# motorDriverv2.net
KiCad netlist of a schematic drawn in Altium Designer
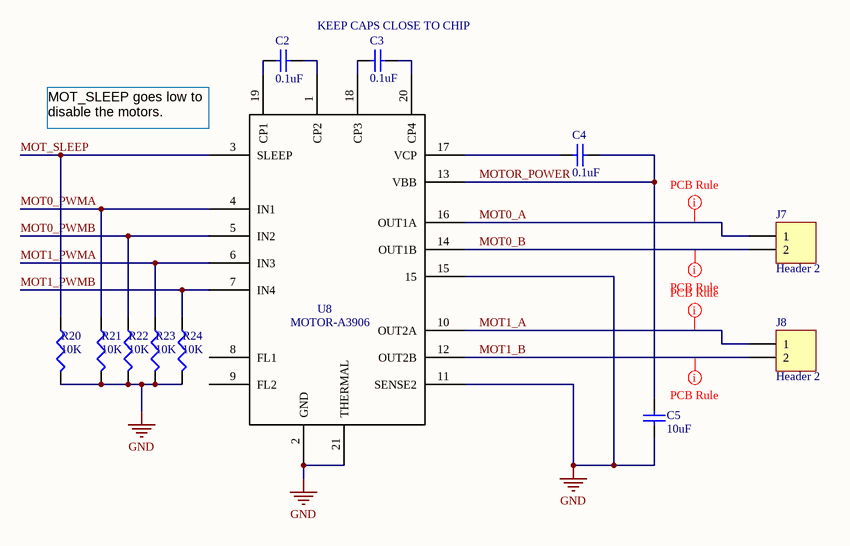
[diagram p0: motorDriverv2.SchDoc]

(export (version "E")
  (design (tool "Eeschema 10.0.6"))
  (components
    (comp (ref "C2")
      (value "0.1uF")
      (footprint "CAPC1005L")
      (description "Capacitor (Semiconductor SIM Model)")
      (fields (field (name "Comment") "Cap Semi") (field (name "PUBLISHER") "Altium Limited"))
      (libsource (lib "Miscellaneous Devices") (part "Cap Semi"))
    )
    (comp (ref "C3")
      (value "0.1uF")
      (footprint "CAPC1005L")
      (description "Capacitor (Semiconductor SIM Model)")
      (fields (field (name "Comment") "Cap Semi") (field (name "PUBLISHER") "Altium Limited"))
      (libsource (lib "Miscellaneous Devices") (part "Cap Semi"))
    )
    (comp (ref "C4")
      (value "0.1uF")
      (footprint "CAPC1005L")
      (description "Capacitor (Semiconductor SIM Model)")
      (fields (field (name "Comment") "Cap Semi") (field (name "PUBLISHER") "Altium Limited"))
      (libsource (lib "Miscellaneous Devices") (part "Cap Semi"))
    )
    (comp (ref "C5")
      (value "10uF")
      (footprint "CAPC1608L")
      (description "Capacitor (Semiconductor SIM Model)")
      (fields (field (name "Comment") "Cap Semi") (field (name "PUBLISHER") "Altium Limited"))
      (libsource (lib "Miscellaneous Devices") (part "Cap Semi"))
    )
    (comp (ref "J7")
      (value "Header 2")
      (footprint "HDR1X2")
      (description "Header, 2-Pin")
      (fields (field (name "PUBLISHER") "Altium Limited"))
      (libsource (lib "mrone") (part "Header 2"))
    )
    (comp (ref "J8")
      (value "Header 2")
      (footprint "HDR1X2")
      (description "Header, 2-Pin")
      (fields (field (name "PUBLISHER") "Altium Limited"))
      (libsource (lib "mrone") (part "Header 2"))
    )
    (comp (ref "R20")
      (value "10K")
      (footprint "J1-0603")
      (description "Resistor")
      (fields (field (name "Comment") "MotorRes") (field (name "PUBLISHER") "Altium Limited"))
      (libsource (lib "Miscellaneous Devices") (part "Res3"))
    )
    (comp (ref "R21")
      (value "10K")
      (footprint "J1-0603")
      (description "Resistor")
      (fields (field (name "Comment") "MotorRes") (field (name "PUBLISHER") "Altium Limited"))
      (libsource (lib "Miscellaneous Devices") (part "Res3"))
    )
    (comp (ref "R22")
      (value "10K")
      (footprint "J1-0603")
      (description "Resistor")
      (fields (field (name "Comment") "MotorRes") (field (name "PUBLISHER") "Altium Limited"))
      (libsource (lib "Miscellaneous Devices") (part "Res3"))
    )
    (comp (ref "R23")
      (value "10K")
      (footprint "J1-0603")
      (description "Resistor")
      (fields (field (name "Comment") "MotorRes") (field (name "PUBLISHER") "Altium Limited"))
      (libsource (lib "Miscellaneous Devices") (part "Res3"))
    )
    (comp (ref "R24")
      (value "10K")
      (footprint "J1-0603")
      (description "Resistor")
      (fields (field (name "Comment") "MotorRes") (field (name "PUBLISHER") "Altium Limited"))
      (libsource (lib "Miscellaneous Devices") (part "Res3"))
    )
    (comp (ref "U8")
      (value "MOTOR-A3906")
      (footprint "QFN-20")
      (libsource (lib "V2_altium") (part "MOTOR-A3906"))
    )
  )
  (nets
    (net (code "1") (name "/MOT0_A") (class "Default")
      (node (ref "J7") (pin "1") (pinfunction "1_1") (pintype "passive"))
      (node (ref "U8") (pin "16") (pinfunction "OUT1A_16") (pintype "passive"))
    )
    (net (code "2") (name "/MOT0_B") (class "Default")
      (node (ref "J7") (pin "2") (pinfunction "2_2") (pintype "passive"))
      (node (ref "U8") (pin "14") (pinfunction "OUT1B_14") (pintype "passive"))
    )
    (net (code "3") (name "/MOT0_PWMA") (class "Default")
      (node (ref "R21") (pin "1") (pinfunction "1_1") (pintype "passive"))
      (node (ref "U8") (pin "4") (pinfunction "IN1_4") (pintype "passive"))
    )
    (net (code "4") (name "/MOT0_PWMB") (class "Default")
      (node (ref "R22") (pin "1") (pinfunction "1_1") (pintype "passive"))
      (node (ref "U8") (pin "5") (pinfunction "IN2_5") (pintype "passive"))
    )
    (net (code "5") (name "/MOT1_A") (class "Default")
      (node (ref "J8") (pin "1") (pinfunction "1_1") (pintype "passive"))
      (node (ref "U8") (pin "10") (pinfunction "OUT2A_10") (pintype "passive"))
    )
    (net (code "6") (name "/MOT1_B") (class "Default")
      (node (ref "J8") (pin "2") (pinfunction "2_2") (pintype "passive"))
      (node (ref "U8") (pin "12") (pinfunction "OUT2B_12") (pintype "passive"))
    )
    (net (code "7") (name "/MOT1_PWMA") (class "Default")
      (node (ref "R23") (pin "1") (pinfunction "1_1") (pintype "passive"))
      (node (ref "U8") (pin "6") (pinfunction "IN3_6") (pintype "passive"))
    )
    (net (code "8") (name "/MOT1_PWMB") (class "Default")
      (node (ref "R24") (pin "1") (pinfunction "1_1") (pintype "passive"))
      (node (ref "U8") (pin "7") (pinfunction "IN4_7") (pintype "passive"))
    )
    (net (code "9") (name "/MOTOR_POWER") (class "Default")
      (node (ref "C4") (pin "2") (pinfunction "2_2") (pintype "passive"))
      (node (ref "C5") (pin "2") (pinfunction "2_2") (pintype "passive"))
      (node (ref "U8") (pin "13") (pinfunction "VBB_13") (pintype "passive"))
    )
    (net (code "10") (name "/MOT_SLEEP") (class "Default")
      (node (ref "R20") (pin "1") (pinfunction "1_1") (pintype "passive"))
      (node (ref "U8") (pin "3") (pinfunction "SLEEP_3") (pintype "passive"))
    )
    (net (code "11") (name "GND") (class "Default")
      (node (ref "C5") (pin "1") (pinfunction "1_1") (pintype "passive"))
      (node (ref "R20") (pin "2") (pinfunction "2_2") (pintype "passive"))
      (node (ref "R21") (pin "2") (pinfunction "2_2") (pintype "passive"))
      (node (ref "R22") (pin "2") (pinfunction "2_2") (pintype "passive"))
      (node (ref "R23") (pin "2") (pinfunction "2_2") (pintype "passive"))
      (node (ref "R24") (pin "2") (pinfunction "2_2") (pintype "passive"))
      (node (ref "U8") (pin "11") (pinfunction "SENSE2_11") (pintype "passive"))
      (node (ref "U8") (pin "15") (pinfunction "15_15") (pintype "passive"))
      (node (ref "U8") (pin "2") (pinfunction "GND_2") (pintype "passive"))
      (node (ref "U8") (pin "21") (pinfunction "THERMAL_21") (pintype "passive"))
    )
    (net (code "12") (name "Net-(U8-CP1)") (class "Default")
      (node (ref "C2") (pin "2") (pinfunction "2_2") (pintype "passive"))
      (node (ref "U8") (pin "19") (pinfunction "CP1_19") (pintype "passive"))
    )
    (net (code "13") (name "Net-(U8-CP2)") (class "Default")
      (node (ref "C2") (pin "1") (pinfunction "1_1") (pintype "passive"))
      (node (ref "U8") (pin "1") (pinfunction "CP2_1") (pintype "passive"))
    )
    (net (code "14") (name "Net-(U8-CP3)") (class "Default")
      (node (ref "C3") (pin "1") (pinfunction "1_1") (pintype "passive"))
      (node (ref "U8") (pin "18") (pinfunction "CP3_18") (pintype "passive"))
    )
    (net (code "15") (name "Net-(U8-CP4)") (class "Default")
      (node (ref "C3") (pin "2") (pinfunction "2_2") (pintype "passive"))
      (node (ref "U8") (pin "20") (pinfunction "CP4_20") (pintype "passive"))
    )
    (net (code "16") (name "Net-(U8-VCP)") (class "Default")
      (node (ref "C4") (pin "1") (pinfunction "1_1") (pintype "passive"))
      (node (ref "U8") (pin "17") (pinfunction "VCP_17") (pintype "passive"))
    )
    (net (code "17") (name "unconnected-(U8-FL1-Pad8)") (class "Default")
      (node (ref "U8") (pin "8") (pinfunction "FL1_8") (pintype "passive"))
    )
    (net (code "18") (name "unconnected-(U8-FL2-Pad9)") (class "Default")
      (node (ref "U8") (pin "9") (pinfunction "FL2_9") (pintype "passive"))
    )
  )
)
